# CAMERA.net
KiCad netlist of a schematic drawn in Altium Designer
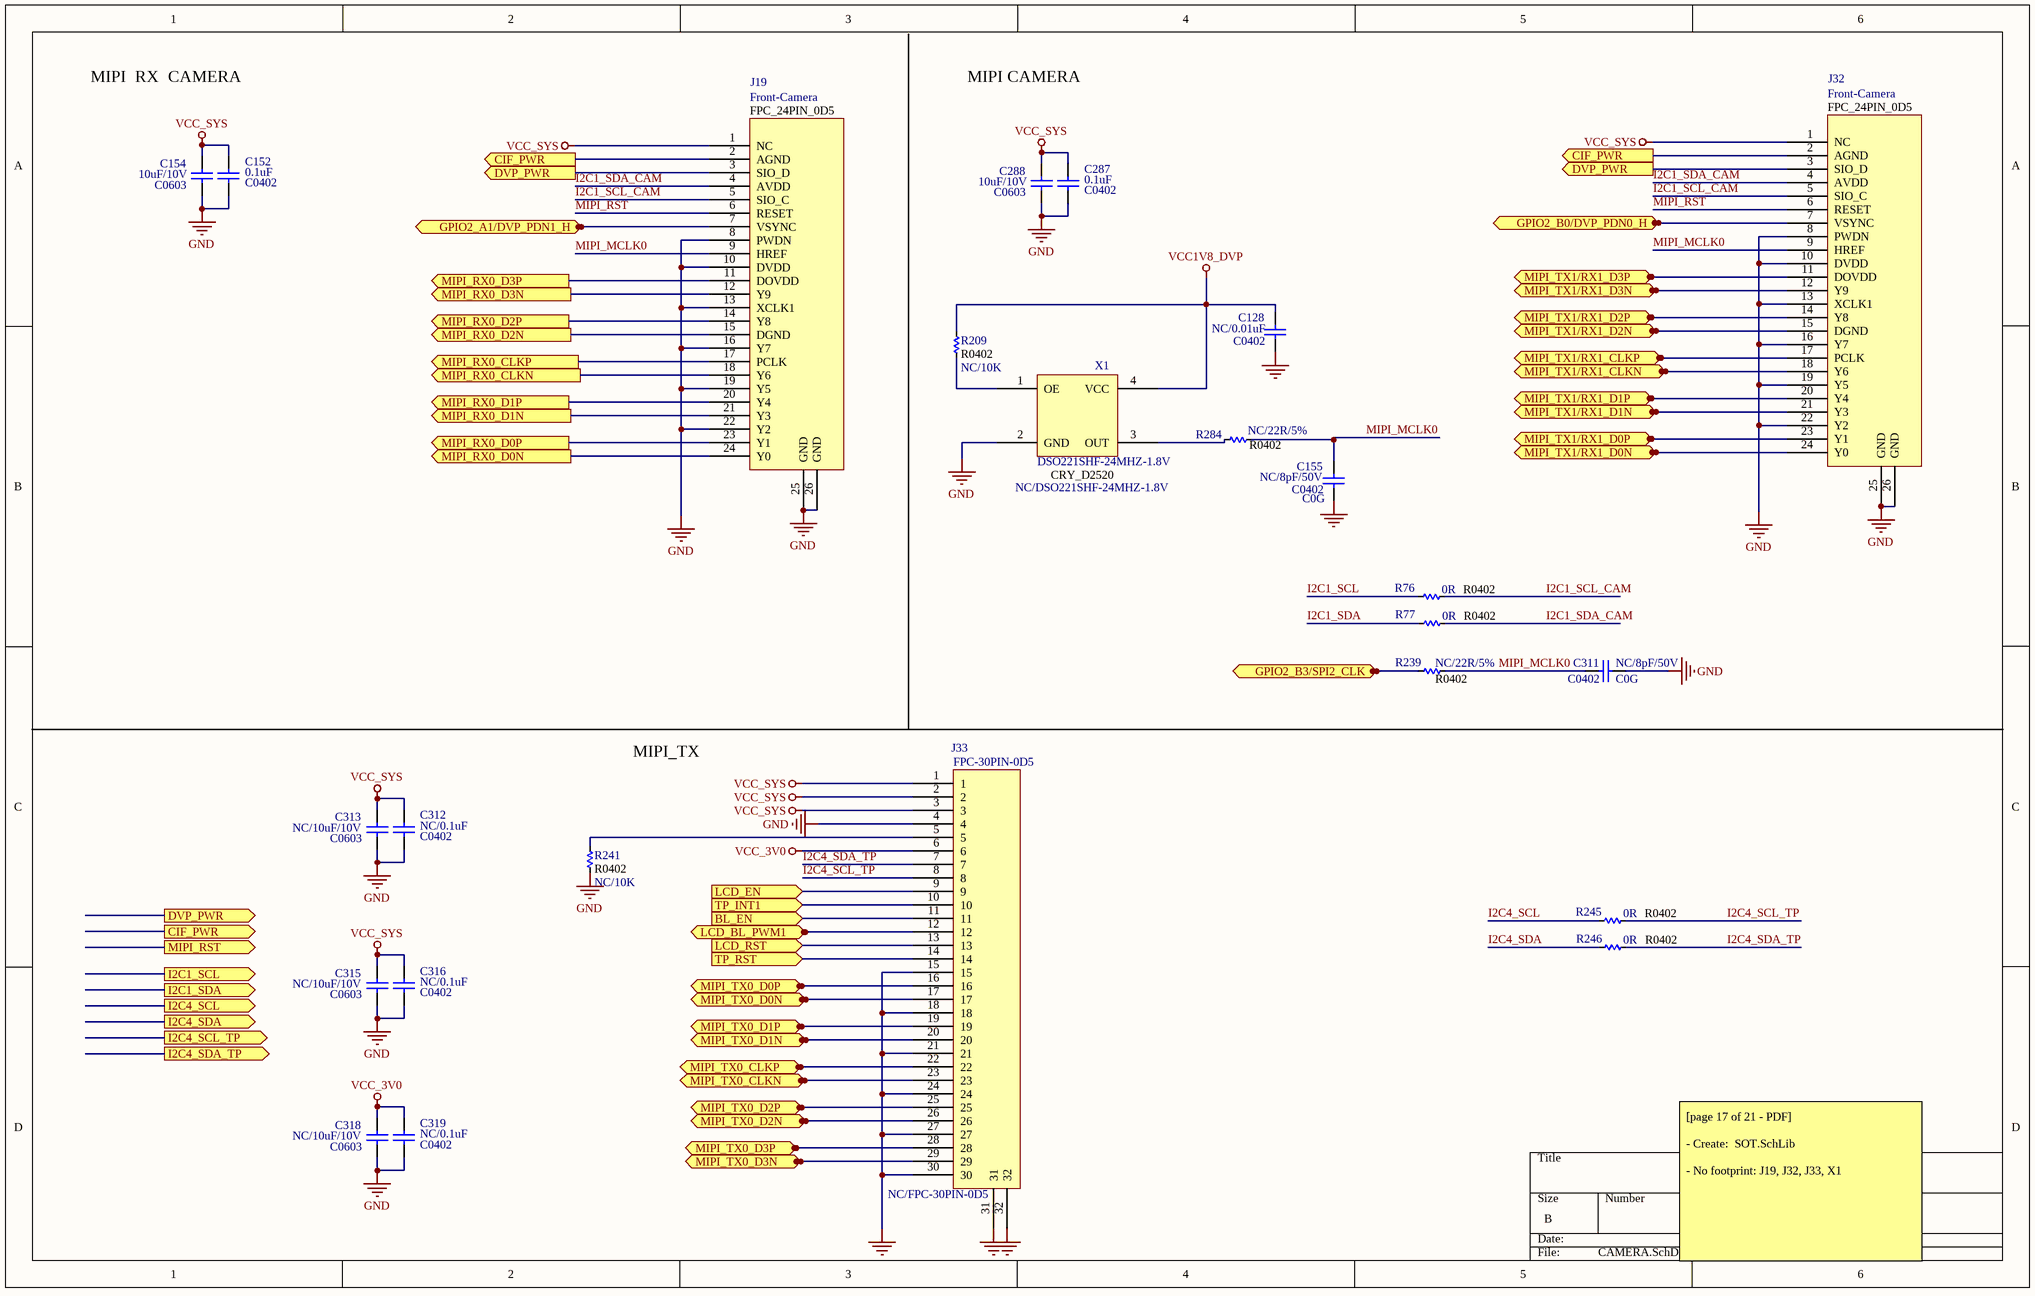
[diagram p0: CAMERA.SchDoc]

(export (version "E")
  (design (tool "Eeschema 10.0.6"))
  (components
    (comp (ref "C128")
      (value "C0402")
      (footprint "C 0402")
      (description "Capacitor")
      (fields (field (name "ALTIUM_VALUE") "NC/0.01uF") (field (name "PUBLISHER") "Altium Limited"))
      (libsource (lib "Miscellaneous Devices") (part "Cap"))
    )
    (comp (ref "C152")
      (value "C0402")
      (footprint "C 0402")
      (description "Capacitor")
      (fields (field (name "ALTIUM_VALUE") "0.1uF") (field (name "PUBLISHER") "Altium Limited"))
      (libsource (lib "Miscellaneous Devices") (part "Cap"))
    )
    (comp (ref "C154")
      (value "C0603")
      (footprint "C 0603")
      (description "Capacitor")
      (fields (field (name "ALTIUM_VALUE") "10uF/10V") (field (name "PUBLISHER") "Altium Limited"))
      (libsource (lib "Miscellaneous Devices") (part "Cap"))
    )
    (comp (ref "C155")
      (value "C0402")
      (footprint "C 0402")
      (description "Capacitor")
      (fields
        (field (name "ALTIUM_VALUE") "NC/8pF/50V")
        (field (name "ALTIUM_UNNAMED_2") "C0G")
        (field (name "PUBLISHER") "Altium Limited")
      )
      (libsource (lib "Miscellaneous Devices") (part "Cap"))
    )
    (comp (ref "C287")
      (value "C0402")
      (footprint "C 0402")
      (description "Capacitor")
      (fields (field (name "ALTIUM_VALUE") "0.1uF") (field (name "PUBLISHER") "Altium Limited"))
      (libsource (lib "Miscellaneous Devices") (part "Cap"))
    )
    (comp (ref "C288")
      (value "C0603")
      (footprint "C 0603")
      (description "Capacitor")
      (fields (field (name "ALTIUM_VALUE") "10uF/10V") (field (name "PUBLISHER") "Altium Limited"))
      (libsource (lib "Miscellaneous Devices") (part "Cap"))
    )
    (comp (ref "C311")
      (value "C0402")
      (footprint "C 0402")
      (description "Capacitor")
      (fields
        (field (name "ALTIUM_VALUE") "NC/8pF/50V")
        (field (name "ALTIUM_UNNAMED_2") "C0G")
        (field (name "PUBLISHER") "Altium Limited")
      )
      (libsource (lib "Miscellaneous Devices") (part "Cap"))
    )
    (comp (ref "C312")
      (value "C0402")
      (footprint "C 0402")
      (description "Capacitor")
      (fields (field (name "ALTIUM_VALUE") "NC/0.1uF") (field (name "PUBLISHER") "Altium Limited"))
      (libsource (lib "Miscellaneous Devices") (part "Cap"))
    )
    (comp (ref "C313")
      (value "C0603")
      (footprint "C 0603")
      (description "Capacitor")
      (fields (field (name "ALTIUM_VALUE") "NC/10uF/10V") (field (name "PUBLISHER") "Altium Limited"))
      (libsource (lib "Miscellaneous Devices") (part "Cap"))
    )
    (comp (ref "C315")
      (value "C0603")
      (footprint "C 0603")
      (description "Capacitor")
      (fields (field (name "ALTIUM_VALUE") "NC/10uF/10V") (field (name "PUBLISHER") "Altium Limited"))
      (libsource (lib "Miscellaneous Devices") (part "Cap"))
    )
    (comp (ref "C316")
      (value "C0402")
      (footprint "C 0402")
      (description "Capacitor")
      (fields (field (name "ALTIUM_VALUE") "NC/0.1uF") (field (name "PUBLISHER") "Altium Limited"))
      (libsource (lib "Miscellaneous Devices") (part "Cap"))
    )
    (comp (ref "C318")
      (value "C0603")
      (footprint "C 0603")
      (description "Capacitor")
      (fields (field (name "ALTIUM_VALUE") "NC/10uF/10V") (field (name "PUBLISHER") "Altium Limited"))
      (libsource (lib "Miscellaneous Devices") (part "Cap"))
    )
    (comp (ref "C319")
      (value "C0402")
      (footprint "C 0402")
      (description "Capacitor")
      (fields (field (name "ALTIUM_VALUE") "NC/0.1uF") (field (name "PUBLISHER") "Altium Limited"))
      (libsource (lib "Miscellaneous Devices") (part "Cap"))
    )
    (comp (ref "J19")
      (value "FPC_24PIN_0D5")
      (footprint "FPC-24Pin")
      (libsource (lib "SOT") (part "FPC_24PIN_0D5"))
    )
    (comp (ref "J32")
      (value "FPC_24PIN_0D5")
      (footprint "FPC-24Pin")
      (libsource (lib "SOT") (part "FPC_24PIN_0D5"))
    )
    (comp (ref "J33")
      (value "NC/FPC-30PIN-0D5")
      (footprint "FPC-30pin")
      (libsource (lib "SOT") (part "FPC-30PIN-0D5"))
    )
    (comp (ref "R76")
      (value "R0402")
      (footprint "R 0402")
      (description "Resistor")
      (fields
        (field (name "MANUFACTURER") "Generic Components")
        (field (name "ALTIUM_VALUE") "0R")
        (field (name "PUBLISHER") "Altium Hobart Technology Centre")
      )
      (libsource (lib "LIBRARY") (part "Res-SMD"))
    )
    (comp (ref "R77")
      (value "R0402")
      (footprint "R 0402")
      (description "Resistor")
      (fields
        (field (name "MANUFACTURER") "Generic Components")
        (field (name "ALTIUM_VALUE") "0R")
        (field (name "PUBLISHER") "Altium Hobart Technology Centre")
      )
      (libsource (lib "LIBRARY") (part "Res-SMD"))
    )
    (comp (ref "R209")
      (value "R0402")
      (footprint "R 0402")
      (description "Resistor")
      (fields
        (field (name "MANUFACTURER") "Generic Components")
        (field (name "ALTIUM_VALUE") "NC/10K")
        (field (name "PUBLISHER") "Altium Hobart Technology Centre")
      )
      (libsource (lib "LIBRARY") (part "Res-SMD"))
    )
    (comp (ref "R239")
      (value "R0402")
      (footprint "R 0402")
      (description "Resistor")
      (fields
        (field (name "MANUFACTURER") "Generic Components")
        (field (name "ALTIUM_VALUE") "NC/22R/5%")
        (field (name "PUBLISHER") "Altium Hobart Technology Centre")
      )
      (libsource (lib "LIBRARY") (part "Res-SMD"))
    )
    (comp (ref "R241")
      (value "R0402")
      (footprint "R 0402")
      (description "Resistor")
      (fields
        (field (name "MANUFACTURER") "Generic Components")
        (field (name "ALTIUM_VALUE") "NC/10K")
        (field (name "PUBLISHER") "Altium Hobart Technology Centre")
      )
      (libsource (lib "LIBRARY") (part "Res-SMD"))
    )
    (comp (ref "R245")
      (value "R0402")
      (footprint "R 0402")
      (description "Resistor")
      (fields
        (field (name "MANUFACTURER") "Generic Components")
        (field (name "ALTIUM_VALUE") "0R")
        (field (name "PUBLISHER") "Altium Hobart Technology Centre")
      )
      (libsource (lib "LIBRARY") (part "Res-SMD"))
    )
    (comp (ref "R246")
      (value "R0402")
      (footprint "R 0402")
      (description "Resistor")
      (fields
        (field (name "MANUFACTURER") "Generic Components")
        (field (name "ALTIUM_VALUE") "0R")
        (field (name "PUBLISHER") "Altium Hobart Technology Centre")
      )
      (libsource (lib "LIBRARY") (part "Res-SMD"))
    )
    (comp (ref "R284")
      (value "R0402")
      (footprint "R 0402")
      (description "Resistor")
      (fields
        (field (name "MANUFACTURER") "Generic Components")
        (field (name "ALTIUM_VALUE") "NC/22R/5%")
        (field (name "PUBLISHER") "Altium Hobart Technology Centre")
      )
      (libsource (lib "LIBRARY") (part "Res-SMD"))
    )
    (comp (ref "X1")
      (value "CRY_D2520")
      (footprint "Crystal 4-SMD 32x25")
      (fields (field (name "ALTIUM_UNNAMED_1") "NC/DSO221SHF-24MHZ-1.8V"))
      (libsource (lib "SOT") (part "CRY_D2520"))
    )
  )
  (nets
    (net (code "1") (name "/BL_EN") (class "Default")
      (node (ref "J33") (pin "11") (pinfunction "11_11") (pintype "passive"))
    )
    (net (code "2") (name "/CIF_PWR") (class "Default")
      (node (ref "J19") (pin "2") (pinfunction "AGND_2") (pintype "passive"))
      (node (ref "J32") (pin "2") (pinfunction "AGND_2") (pintype "passive"))
    )
    (net (code "3") (name "/DVP_PWR") (class "Default")
      (node (ref "J19") (pin "3") (pinfunction "SIO_D_3") (pintype "passive"))
      (node (ref "J32") (pin "3") (pinfunction "SIO_D_3") (pintype "passive"))
    )
    (net (code "4") (name "/GPIO2_A1{slash}DVP_PDN1_H") (class "Default")
      (node (ref "J19") (pin "7") (pinfunction "VSYNC_7") (pintype "passive"))
    )
    (net (code "5") (name "/GPIO2_B0{slash}DVP_PDN0_H") (class "Default")
      (node (ref "J32") (pin "7") (pinfunction "VSYNC_7") (pintype "passive"))
    )
    (net (code "6") (name "/GPIO2_B3{slash}SPI2_CLK") (class "Default")
      (node (ref "R239") (pin "1") (pinfunction "1_1") (pintype "passive"))
    )
    (net (code "7") (name "/I2C1_SCL") (class "Default")
      (node (ref "R76") (pin "1") (pinfunction "1_1") (pintype "passive"))
    )
    (net (code "8") (name "/I2C1_SCL_CAM") (class "Default")
      (node (ref "J19") (pin "5") (pinfunction "SIO_C_5") (pintype "passive"))
      (node (ref "J32") (pin "5") (pinfunction "SIO_C_5") (pintype "passive"))
      (node (ref "R76") (pin "2") (pinfunction "2_2") (pintype "passive"))
    )
    (net (code "9") (name "/I2C1_SDA") (class "Default")
      (node (ref "R77") (pin "1") (pinfunction "1_1") (pintype "passive"))
    )
    (net (code "10") (name "/I2C1_SDA_CAM") (class "Default")
      (node (ref "J19") (pin "4") (pinfunction "AVDD_4") (pintype "passive"))
      (node (ref "J32") (pin "4") (pinfunction "AVDD_4") (pintype "passive"))
      (node (ref "R77") (pin "2") (pinfunction "2_2") (pintype "passive"))
    )
    (net (code "11") (name "/I2C4_SCL") (class "Default")
      (node (ref "R245") (pin "1") (pinfunction "1_1") (pintype "passive"))
    )
    (net (code "12") (name "/I2C4_SCL_TP") (class "Default")
      (node (ref "J33") (pin "8") (pinfunction "8_8") (pintype "passive"))
      (node (ref "R245") (pin "2") (pinfunction "2_2") (pintype "passive"))
    )
    (net (code "13") (name "/I2C4_SDA") (class "Default")
      (node (ref "R246") (pin "1") (pinfunction "1_1") (pintype "passive"))
    )
    (net (code "14") (name "/I2C4_SDA_TP") (class "Default")
      (node (ref "J33") (pin "7") (pinfunction "7_7") (pintype "passive"))
      (node (ref "R246") (pin "2") (pinfunction "2_2") (pintype "passive"))
    )
    (net (code "15") (name "/LCD_BL_PWM1") (class "Default")
      (node (ref "J33") (pin "12") (pinfunction "12_12") (pintype "passive"))
    )
    (net (code "16") (name "/LCD_EN") (class "Default")
      (node (ref "J33") (pin "9") (pinfunction "9_9") (pintype "passive"))
    )
    (net (code "17") (name "/LCD_RST") (class "Default")
      (node (ref "J33") (pin "13") (pinfunction "13_13") (pintype "passive"))
    )
    (net (code "18") (name "/MIPI_MCLK0") (class "Default")
      (node (ref "C155") (pin "1") (pinfunction "1_1") (pintype "passive"))
      (node (ref "C311") (pin "1") (pinfunction "1_1") (pintype "passive"))
      (node (ref "J19") (pin "9") (pinfunction "HREF_9") (pintype "passive"))
      (node (ref "J32") (pin "9") (pinfunction "HREF_9") (pintype "passive"))
      (node (ref "R239") (pin "2") (pinfunction "2_2") (pintype "passive"))
      (node (ref "R284") (pin "2") (pinfunction "2_2") (pintype "passive"))
    )
    (net (code "19") (name "/MIPI_RST") (class "Default")
      (node (ref "J19") (pin "6") (pinfunction "RESET_6") (pintype "passive"))
      (node (ref "J32") (pin "6") (pinfunction "RESET_6") (pintype "passive"))
    )
    (net (code "20") (name "/MIPI_RX0_CLKN") (class "Default")
      (node (ref "J19") (pin "18") (pinfunction "Y6_18") (pintype "passive"))
    )
    (net (code "21") (name "/MIPI_RX0_CLKP") (class "Default")
      (node (ref "J19") (pin "17") (pinfunction "PCLK_17") (pintype "passive"))
    )
    (net (code "22") (name "/MIPI_RX0_D0N") (class "Default")
      (node (ref "J19") (pin "24") (pinfunction "Y0_24") (pintype "passive"))
    )
    (net (code "23") (name "/MIPI_RX0_D0P") (class "Default")
      (node (ref "J19") (pin "23") (pinfunction "Y1_23") (pintype "passive"))
    )
    (net (code "24") (name "/MIPI_RX0_D1N") (class "Default")
      (node (ref "J19") (pin "21") (pinfunction "Y3_21") (pintype "passive"))
    )
    (net (code "25") (name "/MIPI_RX0_D1P") (class "Default")
      (node (ref "J19") (pin "20") (pinfunction "Y4_20") (pintype "passive"))
    )
    (net (code "26") (name "/MIPI_RX0_D2N") (class "Default")
      (node (ref "J19") (pin "15") (pinfunction "DGND_15") (pintype "passive"))
    )
    (net (code "27") (name "/MIPI_RX0_D2P") (class "Default")
      (node (ref "J19") (pin "14") (pinfunction "Y8_14") (pintype "passive"))
    )
    (net (code "28") (name "/MIPI_RX0_D3N") (class "Default")
      (node (ref "J19") (pin "12") (pinfunction "Y9_12") (pintype "passive"))
    )
    (net (code "29") (name "/MIPI_RX0_D3P") (class "Default")
      (node (ref "J19") (pin "11") (pinfunction "DOVDD_11") (pintype "passive"))
    )
    (net (code "30") (name "/MIPI_TX0_CLKN") (class "Default")
      (node (ref "J33") (pin "23") (pinfunction "23_23") (pintype "passive"))
    )
    (net (code "31") (name "/MIPI_TX0_CLKP") (class "Default")
      (node (ref "J33") (pin "22") (pinfunction "22_22") (pintype "passive"))
    )
    (net (code "32") (name "/MIPI_TX0_D0N") (class "Default")
      (node (ref "J33") (pin "17") (pinfunction "17_17") (pintype "passive"))
    )
    (net (code "33") (name "/MIPI_TX0_D0P") (class "Default")
      (node (ref "J33") (pin "16") (pinfunction "16_16") (pintype "passive"))
    )
    (net (code "34") (name "/MIPI_TX0_D1N") (class "Default")
      (node (ref "J33") (pin "20") (pinfunction "20_20") (pintype "passive"))
    )
    (net (code "35") (name "/MIPI_TX0_D1P") (class "Default")
      (node (ref "J33") (pin "19") (pinfunction "19_19") (pintype "passive"))
    )
    (net (code "36") (name "/MIPI_TX0_D2N") (class "Default")
      (node (ref "J33") (pin "26") (pinfunction "26_26") (pintype "passive"))
    )
    (net (code "37") (name "/MIPI_TX0_D2P") (class "Default")
      (node (ref "J33") (pin "25") (pinfunction "25_25") (pintype "passive"))
    )
    (net (code "38") (name "/MIPI_TX0_D3N") (class "Default")
      (node (ref "J33") (pin "29") (pinfunction "29_29") (pintype "passive"))
    )
    (net (code "39") (name "/MIPI_TX0_D3P") (class "Default")
      (node (ref "J33") (pin "28") (pinfunction "28_28") (pintype "passive"))
    )
    (net (code "40") (name "/MIPI_TX1{slash}RX1_CLKN") (class "Default")
      (node (ref "J32") (pin "18") (pinfunction "Y6_18") (pintype "passive"))
    )
    (net (code "41") (name "/MIPI_TX1{slash}RX1_CLKP") (class "Default")
      (node (ref "J32") (pin "17") (pinfunction "PCLK_17") (pintype "passive"))
    )
    (net (code "42") (name "/MIPI_TX1{slash}RX1_D0N") (class "Default")
      (node (ref "J32") (pin "24") (pinfunction "Y0_24") (pintype "passive"))
    )
    (net (code "43") (name "/MIPI_TX1{slash}RX1_D0P") (class "Default")
      (node (ref "J32") (pin "23") (pinfunction "Y1_23") (pintype "passive"))
    )
    (net (code "44") (name "/MIPI_TX1{slash}RX1_D1N") (class "Default")
      (node (ref "J32") (pin "21") (pinfunction "Y3_21") (pintype "passive"))
    )
    (net (code "45") (name "/MIPI_TX1{slash}RX1_D1P") (class "Default")
      (node (ref "J32") (pin "20") (pinfunction "Y4_20") (pintype "passive"))
    )
    (net (code "46") (name "/MIPI_TX1{slash}RX1_D2N") (class "Default")
      (node (ref "J32") (pin "15") (pinfunction "DGND_15") (pintype "passive"))
    )
    (net (code "47") (name "/MIPI_TX1{slash}RX1_D2P") (class "Default")
      (node (ref "J32") (pin "14") (pinfunction "Y8_14") (pintype "passive"))
    )
    (net (code "48") (name "/MIPI_TX1{slash}RX1_D3N") (class "Default")
      (node (ref "J32") (pin "12") (pinfunction "Y9_12") (pintype "passive"))
    )
    (net (code "49") (name "/MIPI_TX1{slash}RX1_D3P") (class "Default")
      (node (ref "J32") (pin "11") (pinfunction "DOVDD_11") (pintype "passive"))
    )
    (net (code "50") (name "/TP_INT1") (class "Default")
      (node (ref "J33") (pin "10") (pinfunction "10_10") (pintype "passive"))
    )
    (net (code "51") (name "/TP_RST") (class "Default")
      (node (ref "J33") (pin "14") (pinfunction "14_14") (pintype "passive"))
    )
    (net (code "52") (name "GND") (class "Default")
      (node (ref "C128") (pin "2") (pinfunction "2_2") (pintype "passive"))
      (node (ref "C152") (pin "2") (pinfunction "2_2") (pintype "passive"))
      (node (ref "C154") (pin "2") (pinfunction "2_2") (pintype "passive"))
      (node (ref "C155") (pin "2") (pinfunction "2_2") (pintype "passive"))
      (node (ref "C287") (pin "2") (pinfunction "2_2") (pintype "passive"))
      (node (ref "C288") (pin "2") (pinfunction "2_2") (pintype "passive"))
      (node (ref "C311") (pin "2") (pinfunction "2_2") (pintype "passive"))
      (node (ref "C312") (pin "2") (pinfunction "2_2") (pintype "passive"))
      (node (ref "C313") (pin "2") (pinfunction "2_2") (pintype "passive"))
      (node (ref "C315") (pin "2") (pinfunction "2_2") (pintype "passive"))
      (node (ref "C316") (pin "2") (pinfunction "2_2") (pintype "passive"))
      (node (ref "C318") (pin "2") (pinfunction "2_2") (pintype "passive"))
      (node (ref "C319") (pin "2") (pinfunction "2_2") (pintype "passive"))
      (node (ref "J19") (pin "10") (pinfunction "DVDD_10") (pintype "passive"))
      (node (ref "J19") (pin "13") (pinfunction "XCLK1_13") (pintype "passive"))
      (node (ref "J19") (pin "16") (pinfunction "Y7_16") (pintype "passive"))
      (node (ref "J19") (pin "19") (pinfunction "Y5_19") (pintype "passive"))
      (node (ref "J19") (pin "22") (pinfunction "Y2_22") (pintype "passive"))
      (node (ref "J19") (pin "25") (pinfunction "GND_25") (pintype "passive"))
      (node (ref "J19") (pin "26") (pinfunction "GND_26") (pintype "passive"))
      (node (ref "J19") (pin "8") (pinfunction "PWDN_8") (pintype "passive"))
      (node (ref "J32") (pin "10") (pinfunction "DVDD_10") (pintype "passive"))
      (node (ref "J32") (pin "13") (pinfunction "XCLK1_13") (pintype "passive"))
      (node (ref "J32") (pin "16") (pinfunction "Y7_16") (pintype "passive"))
      (node (ref "J32") (pin "19") (pinfunction "Y5_19") (pintype "passive"))
      (node (ref "J32") (pin "22") (pinfunction "Y2_22") (pintype "passive"))
      (node (ref "J32") (pin "25") (pinfunction "GND_25") (pintype "passive"))
      (node (ref "J32") (pin "26") (pinfunction "GND_26") (pintype "passive"))
      (node (ref "J32") (pin "8") (pinfunction "PWDN_8") (pintype "passive"))
      (node (ref "J33") (pin "15") (pinfunction "15_15") (pintype "passive"))
      (node (ref "J33") (pin "18") (pinfunction "18_18") (pintype "passive"))
      (node (ref "J33") (pin "21") (pinfunction "21_21") (pintype "passive"))
      (node (ref "J33") (pin "24") (pinfunction "24_24") (pintype "passive"))
      (node (ref "J33") (pin "27") (pinfunction "27_27") (pintype "passive"))
      (node (ref "J33") (pin "30") (pinfunction "30_30") (pintype "passive"))
      (node (ref "J33") (pin "31") (pinfunction "31_31") (pintype "passive"))
      (node (ref "J33") (pin "32") (pinfunction "32_32") (pintype "passive"))
      (node (ref "J33") (pin "4") (pinfunction "4_4") (pintype "passive"))
      (node (ref "R241") (pin "2") (pinfunction "2_2") (pintype "passive"))
      (node (ref "X1") (pin "2") (pinfunction "GND_2") (pintype "passive"))
    )
    (net (code "53") (name "Net-(J33-Pad5)") (class "Default")
      (node (ref "J33") (pin "5") (pinfunction "5_5") (pintype "passive"))
      (node (ref "R241") (pin "1") (pinfunction "1_1") (pintype "passive"))
    )
    (net (code "54") (name "Net-(X1-OE)") (class "Default")
      (node (ref "R209") (pin "2") (pinfunction "2_2") (pintype "passive"))
      (node (ref "X1") (pin "1") (pinfunction "OE_1") (pintype "passive"))
    )
    (net (code "55") (name "Net-(X1-OUT)") (class "Default")
      (node (ref "R284") (pin "1") (pinfunction "1_1") (pintype "passive"))
      (node (ref "X1") (pin "3") (pinfunction "OUT_3") (pintype "passive"))
    )
    (net (code "56") (name "VCC1V8_DVP") (class "Default")
      (node (ref "C128") (pin "1") (pinfunction "1_1") (pintype "passive"))
      (node (ref "R209") (pin "1") (pinfunction "1_1") (pintype "passive"))
      (node (ref "X1") (pin "4") (pinfunction "VCC_4") (pintype "passive"))
    )
    (net (code "57") (name "VCC_3V0") (class "Default")
      (node (ref "C318") (pin "1") (pinfunction "1_1") (pintype "passive"))
      (node (ref "C319") (pin "1") (pinfunction "1_1") (pintype "passive"))
      (node (ref "J33") (pin "6") (pinfunction "6_6") (pintype "passive"))
    )
    (net (code "58") (name "VCC_SYS") (class "Default")
      (node (ref "C152") (pin "1") (pinfunction "1_1") (pintype "passive"))
      (node (ref "C154") (pin "1") (pinfunction "1_1") (pintype "passive"))
      (node (ref "C287") (pin "1") (pinfunction "1_1") (pintype "passive"))
      (node (ref "C288") (pin "1") (pinfunction "1_1") (pintype "passive"))
      (node (ref "C312") (pin "1") (pinfunction "1_1") (pintype "passive"))
      (node (ref "C313") (pin "1") (pinfunction "1_1") (pintype "passive"))
      (node (ref "C315") (pin "1") (pinfunction "1_1") (pintype "passive"))
      (node (ref "C316") (pin "1") (pinfunction "1_1") (pintype "passive"))
      (node (ref "J19") (pin "1") (pinfunction "NC_1") (pintype "passive"))
      (node (ref "J32") (pin "1") (pinfunction "NC_1") (pintype "passive"))
      (node (ref "J33") (pin "1") (pinfunction "1_1") (pintype "passive"))
      (node (ref "J33") (pin "2") (pinfunction "2_2") (pintype "passive"))
      (node (ref "J33") (pin "3") (pinfunction "3_3") (pintype "passive"))
    )
  )
)
